# arduino_board.net
KiCad netlist of a schematic drawn in EAGLE
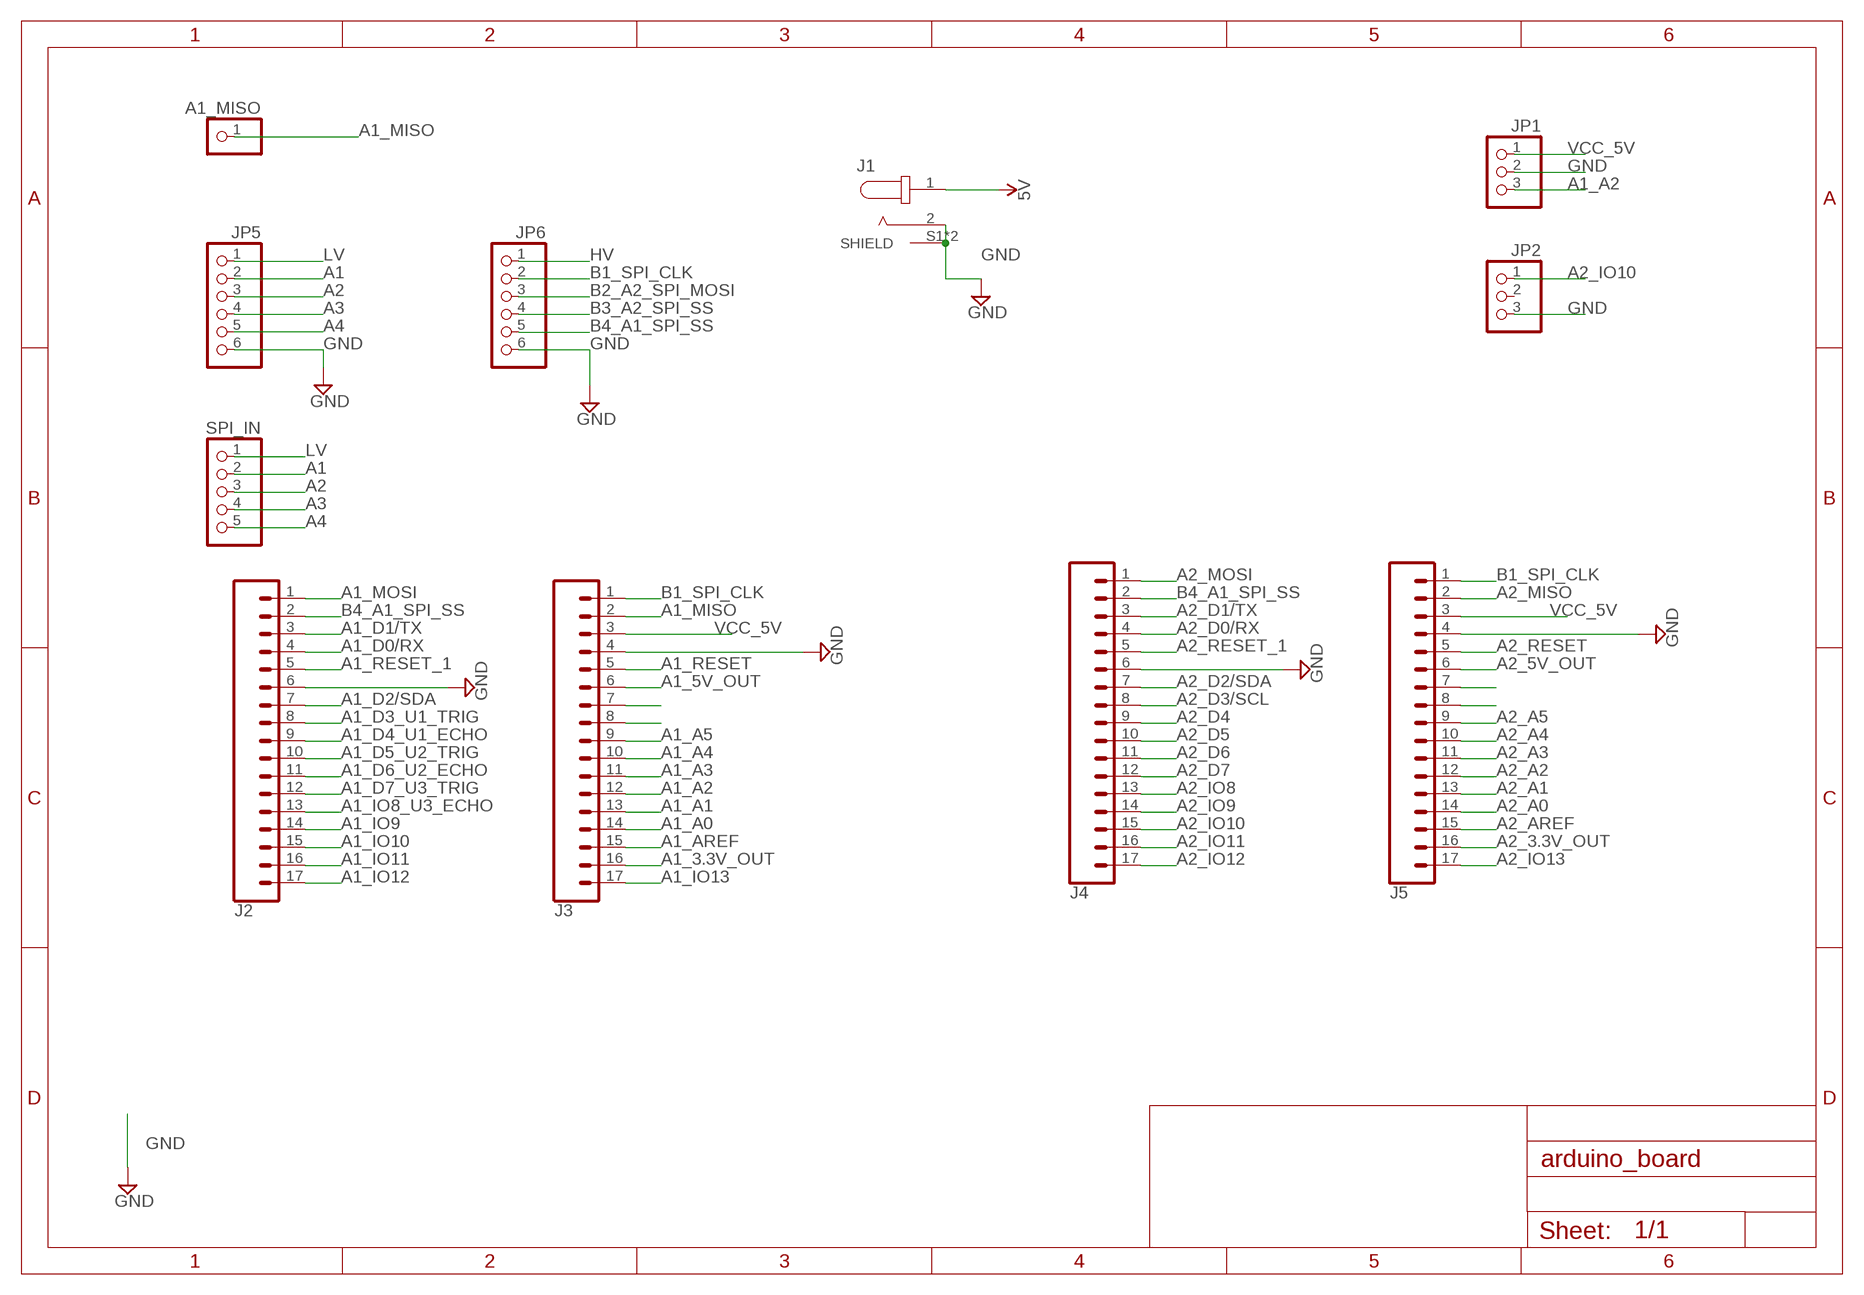
[diagram p0: schematic, sheet 1]

(export (version "E")
  (design (tool "Eeschema 10.0.6"))
  (components
    (comp (ref "A1_MISO")
      (value "PINHD-1X1")
      (footprint "eagle-import:1X01")
      (libsource (lib "eagle-import") (part "PINHD-1X1"))
    )
    (comp (ref "J1")
      (value "PJ-063AH")
      (footprint "eagle-import:CUI_PJ-063AH")
      (fields (field (name "MF") "CUI Inc."))
      (libsource (lib "eagle-import") (part "PJ-063AH"))
    )
    (comp (ref "J2")
      (value "CONN_17")
      (footprint "eagle-import:1X17")
      (libsource (lib "eagle-import") (part "CONN_17"))
    )
    (comp (ref "J3")
      (value "CONN_17")
      (footprint "eagle-import:1X17")
      (libsource (lib "eagle-import") (part "CONN_17"))
    )
    (comp (ref "J4")
      (value "CONN_17")
      (footprint "eagle-import:1X17")
      (libsource (lib "eagle-import") (part "CONN_17"))
    )
    (comp (ref "J5")
      (value "CONN_17")
      (footprint "eagle-import:1X17")
      (libsource (lib "eagle-import") (part "CONN_17"))
    )
    (comp (ref "JP1")
      (value "PINHD-1X3")
      (footprint "eagle-import:1X03")
      (libsource (lib "eagle-import") (part "PINHD-1X3"))
    )
    (comp (ref "JP2")
      (value "PINHD-1X3")
      (footprint "eagle-import:1X03")
      (libsource (lib "eagle-import") (part "PINHD-1X3"))
    )
    (comp (ref "JP5")
      (value "PINHD-1X6")
      (footprint "eagle-import:1X06")
      (libsource (lib "eagle-import") (part "PINHD-1X6"))
    )
    (comp (ref "JP6")
      (value "PINHD-1X6")
      (footprint "eagle-import:1X06")
      (libsource (lib "eagle-import") (part "PINHD-1X6"))
    )
    (comp (ref "SPI_IN")
      (value "PINHD-1X5")
      (footprint "eagle-import:1X05")
      (libsource (lib "eagle-import") (part "PINHD-1X5"))
    )
  )
  (nets
    (net (code "1") (name "/A1") (class "Default")
      (node (ref "JP5") (pin "2") (pinfunction "2_2") (pintype "passive"))
      (node (ref "SPI_IN") (pin "2") (pinfunction "2_2") (pintype "passive"))
    )
    (net (code "2") (name "/A1_3.3V_OUT") (class "Default")
      (node (ref "J3") (pin "16") (pinfunction "16_16") (pintype "passive"))
    )
    (net (code "3") (name "/A1_5V_OUT") (class "Default")
      (node (ref "J3") (pin "6") (pinfunction "6_6") (pintype "passive"))
    )
    (net (code "4") (name "/A1_A0") (class "Default")
      (node (ref "J3") (pin "14") (pinfunction "14_14") (pintype "passive"))
    )
    (net (code "5") (name "/A1_A1") (class "Default")
      (node (ref "J3") (pin "13") (pinfunction "13_13") (pintype "passive"))
    )
    (net (code "6") (name "/A1_A2") (class "Default")
      (node (ref "J3") (pin "12") (pinfunction "12_12") (pintype "passive"))
      (node (ref "JP1") (pin "3") (pinfunction "3_3") (pintype "passive"))
    )
    (net (code "7") (name "/A1_A3") (class "Default")
      (node (ref "J3") (pin "11") (pinfunction "11_11") (pintype "passive"))
    )
    (net (code "8") (name "/A1_A4") (class "Default")
      (node (ref "J3") (pin "10") (pinfunction "10_10") (pintype "passive"))
    )
    (net (code "9") (name "/A1_A5") (class "Default")
      (node (ref "J3") (pin "9") (pinfunction "9_9") (pintype "passive"))
    )
    (net (code "10") (name "/A1_AREF") (class "Default")
      (node (ref "J3") (pin "15") (pinfunction "15_15") (pintype "passive"))
    )
    (net (code "11") (name "/A1_D0{slash}RX") (class "Default")
      (node (ref "J2") (pin "4") (pinfunction "4_4") (pintype "passive"))
    )
    (net (code "12") (name "/A1_D1{slash}TX") (class "Default")
      (node (ref "J2") (pin "3") (pinfunction "3_3") (pintype "passive"))
    )
    (net (code "13") (name "/A1_D2{slash}SDA") (class "Default")
      (node (ref "J2") (pin "7") (pinfunction "7_7") (pintype "passive"))
    )
    (net (code "14") (name "/A1_D3_U1_TRIG") (class "Default")
      (node (ref "J2") (pin "8") (pinfunction "8_8") (pintype "passive"))
    )
    (net (code "15") (name "/A1_D4_U1_ECHO") (class "Default")
      (node (ref "J2") (pin "9") (pinfunction "9_9") (pintype "passive"))
    )
    (net (code "16") (name "/A1_D5_U2_TRIG") (class "Default")
      (node (ref "J2") (pin "10") (pinfunction "10_10") (pintype "passive"))
    )
    (net (code "17") (name "/A1_D6_U2_ECHO") (class "Default")
      (node (ref "J2") (pin "11") (pinfunction "11_11") (pintype "passive"))
    )
    (net (code "18") (name "/A1_D7_U3_TRIG") (class "Default")
      (node (ref "J2") (pin "12") (pinfunction "12_12") (pintype "passive"))
    )
    (net (code "19") (name "/A1_IO8_U3_ECHO") (class "Default")
      (node (ref "J2") (pin "13") (pinfunction "13_13") (pintype "passive"))
    )
    (net (code "20") (name "/A1_IO9") (class "Default")
      (node (ref "J2") (pin "14") (pinfunction "14_14") (pintype "passive"))
    )
    (net (code "21") (name "/A1_IO10") (class "Default")
      (node (ref "J2") (pin "15") (pinfunction "15_15") (pintype "passive"))
    )
    (net (code "22") (name "/A1_IO11") (class "Default")
      (node (ref "J2") (pin "16") (pinfunction "16_16") (pintype "passive"))
    )
    (net (code "23") (name "/A1_IO12") (class "Default")
      (node (ref "J2") (pin "17") (pinfunction "17_17") (pintype "passive"))
    )
    (net (code "24") (name "/A1_IO13") (class "Default")
      (node (ref "J3") (pin "17") (pinfunction "17_17") (pintype "passive"))
    )
    (net (code "25") (name "/A1_MISO") (class "Default")
      (node (ref "A1_MISO") (pin "1") (pinfunction "1_1") (pintype "passive"))
      (node (ref "J3") (pin "2") (pinfunction "2_2") (pintype "passive"))
    )
    (net (code "26") (name "/A1_MOSI") (class "Default")
      (node (ref "J2") (pin "1") (pinfunction "1_1") (pintype "passive"))
    )
    (net (code "27") (name "/A1_RESET") (class "Default")
      (node (ref "J3") (pin "5") (pinfunction "5_5") (pintype "passive"))
    )
    (net (code "28") (name "/A1_RESET_1") (class "Default")
      (node (ref "J2") (pin "5") (pinfunction "5_5") (pintype "passive"))
    )
    (net (code "29") (name "/A2") (class "Default")
      (node (ref "JP5") (pin "3") (pinfunction "3_3") (pintype "passive"))
      (node (ref "SPI_IN") (pin "3") (pinfunction "3_3") (pintype "passive"))
    )
    (net (code "30") (name "/A2_3.3V_OUT") (class "Default")
      (node (ref "J5") (pin "16") (pinfunction "16_16") (pintype "passive"))
    )
    (net (code "31") (name "/A2_5V_OUT") (class "Default")
      (node (ref "J5") (pin "6") (pinfunction "6_6") (pintype "passive"))
    )
    (net (code "32") (name "/A2_A0") (class "Default")
      (node (ref "J5") (pin "14") (pinfunction "14_14") (pintype "passive"))
    )
    (net (code "33") (name "/A2_A1") (class "Default")
      (node (ref "J5") (pin "13") (pinfunction "13_13") (pintype "passive"))
    )
    (net (code "34") (name "/A2_A2") (class "Default")
      (node (ref "J5") (pin "12") (pinfunction "12_12") (pintype "passive"))
    )
    (net (code "35") (name "/A2_A3") (class "Default")
      (node (ref "J5") (pin "11") (pinfunction "11_11") (pintype "passive"))
    )
    (net (code "36") (name "/A2_A4") (class "Default")
      (node (ref "J5") (pin "10") (pinfunction "10_10") (pintype "passive"))
    )
    (net (code "37") (name "/A2_A5") (class "Default")
      (node (ref "J5") (pin "9") (pinfunction "9_9") (pintype "passive"))
    )
    (net (code "38") (name "/A2_AREF") (class "Default")
      (node (ref "J5") (pin "15") (pinfunction "15_15") (pintype "passive"))
    )
    (net (code "39") (name "/A2_D0{slash}RX") (class "Default")
      (node (ref "J4") (pin "4") (pinfunction "4_4") (pintype "passive"))
    )
    (net (code "40") (name "/A2_D1{slash}TX") (class "Default")
      (node (ref "J4") (pin "3") (pinfunction "3_3") (pintype "passive"))
    )
    (net (code "41") (name "/A2_D2{slash}SDA") (class "Default")
      (node (ref "J4") (pin "7") (pinfunction "7_7") (pintype "passive"))
    )
    (net (code "42") (name "/A2_D3{slash}SCL") (class "Default")
      (node (ref "J4") (pin "8") (pinfunction "8_8") (pintype "passive"))
    )
    (net (code "43") (name "/A2_D4") (class "Default")
      (node (ref "J4") (pin "9") (pinfunction "9_9") (pintype "passive"))
    )
    (net (code "44") (name "/A2_D5") (class "Default")
      (node (ref "J4") (pin "10") (pinfunction "10_10") (pintype "passive"))
    )
    (net (code "45") (name "/A2_D6") (class "Default")
      (node (ref "J4") (pin "11") (pinfunction "11_11") (pintype "passive"))
    )
    (net (code "46") (name "/A2_D7") (class "Default")
      (node (ref "J4") (pin "12") (pinfunction "12_12") (pintype "passive"))
    )
    (net (code "47") (name "/A2_IO8") (class "Default")
      (node (ref "J4") (pin "13") (pinfunction "13_13") (pintype "passive"))
    )
    (net (code "48") (name "/A2_IO9") (class "Default")
      (node (ref "J4") (pin "14") (pinfunction "14_14") (pintype "passive"))
    )
    (net (code "49") (name "/A2_IO10") (class "Default")
      (node (ref "J4") (pin "15") (pinfunction "15_15") (pintype "passive"))
      (node (ref "JP2") (pin "1") (pinfunction "1_1") (pintype "passive"))
    )
    (net (code "50") (name "/A2_IO11") (class "Default")
      (node (ref "J4") (pin "16") (pinfunction "16_16") (pintype "passive"))
    )
    (net (code "51") (name "/A2_IO12") (class "Default")
      (node (ref "J4") (pin "17") (pinfunction "17_17") (pintype "passive"))
    )
    (net (code "52") (name "/A2_IO13") (class "Default")
      (node (ref "J5") (pin "17") (pinfunction "17_17") (pintype "passive"))
    )
    (net (code "53") (name "/A2_MISO") (class "Default")
      (node (ref "J5") (pin "2") (pinfunction "2_2") (pintype "passive"))
    )
    (net (code "54") (name "/A2_MOSI") (class "Default")
      (node (ref "J4") (pin "1") (pinfunction "1_1") (pintype "passive"))
    )
    (net (code "55") (name "/A2_RESET") (class "Default")
      (node (ref "J5") (pin "5") (pinfunction "5_5") (pintype "passive"))
    )
    (net (code "56") (name "/A2_RESET_1") (class "Default")
      (node (ref "J4") (pin "5") (pinfunction "5_5") (pintype "passive"))
    )
    (net (code "57") (name "/A3") (class "Default")
      (node (ref "JP5") (pin "4") (pinfunction "4_4") (pintype "passive"))
      (node (ref "SPI_IN") (pin "4") (pinfunction "4_4") (pintype "passive"))
    )
    (net (code "58") (name "/A4") (class "Default")
      (node (ref "JP5") (pin "5") (pinfunction "5_5") (pintype "passive"))
      (node (ref "SPI_IN") (pin "5") (pinfunction "5_5") (pintype "passive"))
    )
    (net (code "59") (name "/B1_SPI_CLK") (class "Default")
      (node (ref "J3") (pin "1") (pinfunction "1_1") (pintype "passive"))
      (node (ref "J5") (pin "1") (pinfunction "1_1") (pintype "passive"))
      (node (ref "JP6") (pin "2") (pinfunction "2_2") (pintype "passive"))
    )
    (net (code "60") (name "/B2_A2_SPI_MOSI") (class "Default")
      (node (ref "JP6") (pin "3") (pinfunction "3_3") (pintype "passive"))
    )
    (net (code "61") (name "/B3_A2_SPI_SS") (class "Default")
      (node (ref "JP6") (pin "4") (pinfunction "4_4") (pintype "passive"))
    )
    (net (code "62") (name "/B4_A1_SPI_SS") (class "Default")
      (node (ref "J2") (pin "2") (pinfunction "2_2") (pintype "passive"))
      (node (ref "J4") (pin "2") (pinfunction "2_2") (pintype "passive"))
      (node (ref "JP6") (pin "5") (pinfunction "5_5") (pintype "passive"))
    )
    (net (code "63") (name "/HV") (class "Default")
      (node (ref "JP6") (pin "1") (pinfunction "1_1") (pintype "passive"))
    )
    (net (code "64") (name "/LV") (class "Default")
      (node (ref "JP5") (pin "1") (pinfunction "1_1") (pintype "passive"))
      (node (ref "SPI_IN") (pin "1") (pinfunction "1_1") (pintype "passive"))
    )
    (net (code "65") (name "/VCC_5V") (class "Default")
      (node (ref "J3") (pin "3") (pinfunction "3_3") (pintype "passive"))
      (node (ref "J5") (pin "3") (pinfunction "3_3") (pintype "passive"))
      (node (ref "JP1") (pin "1") (pinfunction "1_1") (pintype "passive"))
    )
    (net (code "66") (name "5V") (class "Default")
      (node (ref "J1") (pin "1") (pinfunction "1_1") (pintype "passive"))
    )
    (net (code "67") (name "GND") (class "Default")
      (node (ref "J1") (pin "2") (pinfunction "2_2") (pintype "passive"))
      (node (ref "J1") (pin "S1") (pinfunction "SHIELD_S1") (pintype "power_in"))
      (node (ref "J1") (pin "S2") (pinfunction "SHIELD_S2") (pintype "power_in"))
      (node (ref "J2") (pin "6") (pinfunction "6_6") (pintype "passive"))
      (node (ref "J3") (pin "4") (pinfunction "4_4") (pintype "passive"))
      (node (ref "J4") (pin "6") (pinfunction "6_6") (pintype "passive"))
      (node (ref "J5") (pin "4") (pinfunction "4_4") (pintype "passive"))
      (node (ref "JP1") (pin "2") (pinfunction "2_2") (pintype "passive"))
      (node (ref "JP2") (pin "3") (pinfunction "3_3") (pintype "passive"))
      (node (ref "JP5") (pin "6") (pinfunction "6_6") (pintype "passive"))
      (node (ref "JP6") (pin "6") (pinfunction "6_6") (pintype "passive"))
    )
    (net (code "68") (name "unconnected-(J3-Pad7)") (class "Default")
      (node (ref "J3") (pin "7") (pinfunction "7_7") (pintype "passive"))
    )
    (net (code "69") (name "unconnected-(J3-Pad8)") (class "Default")
      (node (ref "J3") (pin "8") (pinfunction "8_8") (pintype "passive"))
    )
    (net (code "70") (name "unconnected-(J5-Pad7)") (class "Default")
      (node (ref "J5") (pin "7") (pinfunction "7_7") (pintype "passive"))
    )
    (net (code "71") (name "unconnected-(J5-Pad8)") (class "Default")
      (node (ref "J5") (pin "8") (pinfunction "8_8") (pintype "passive"))
    )
    (net (code "72") (name "unconnected-(JP2-Pad2)") (class "Default")
      (node (ref "JP2") (pin "2") (pinfunction "2_2") (pintype "passive"))
    )
  )
)
